# 1_Power.net
KiCad netlist of a schematic drawn in Altium Designer
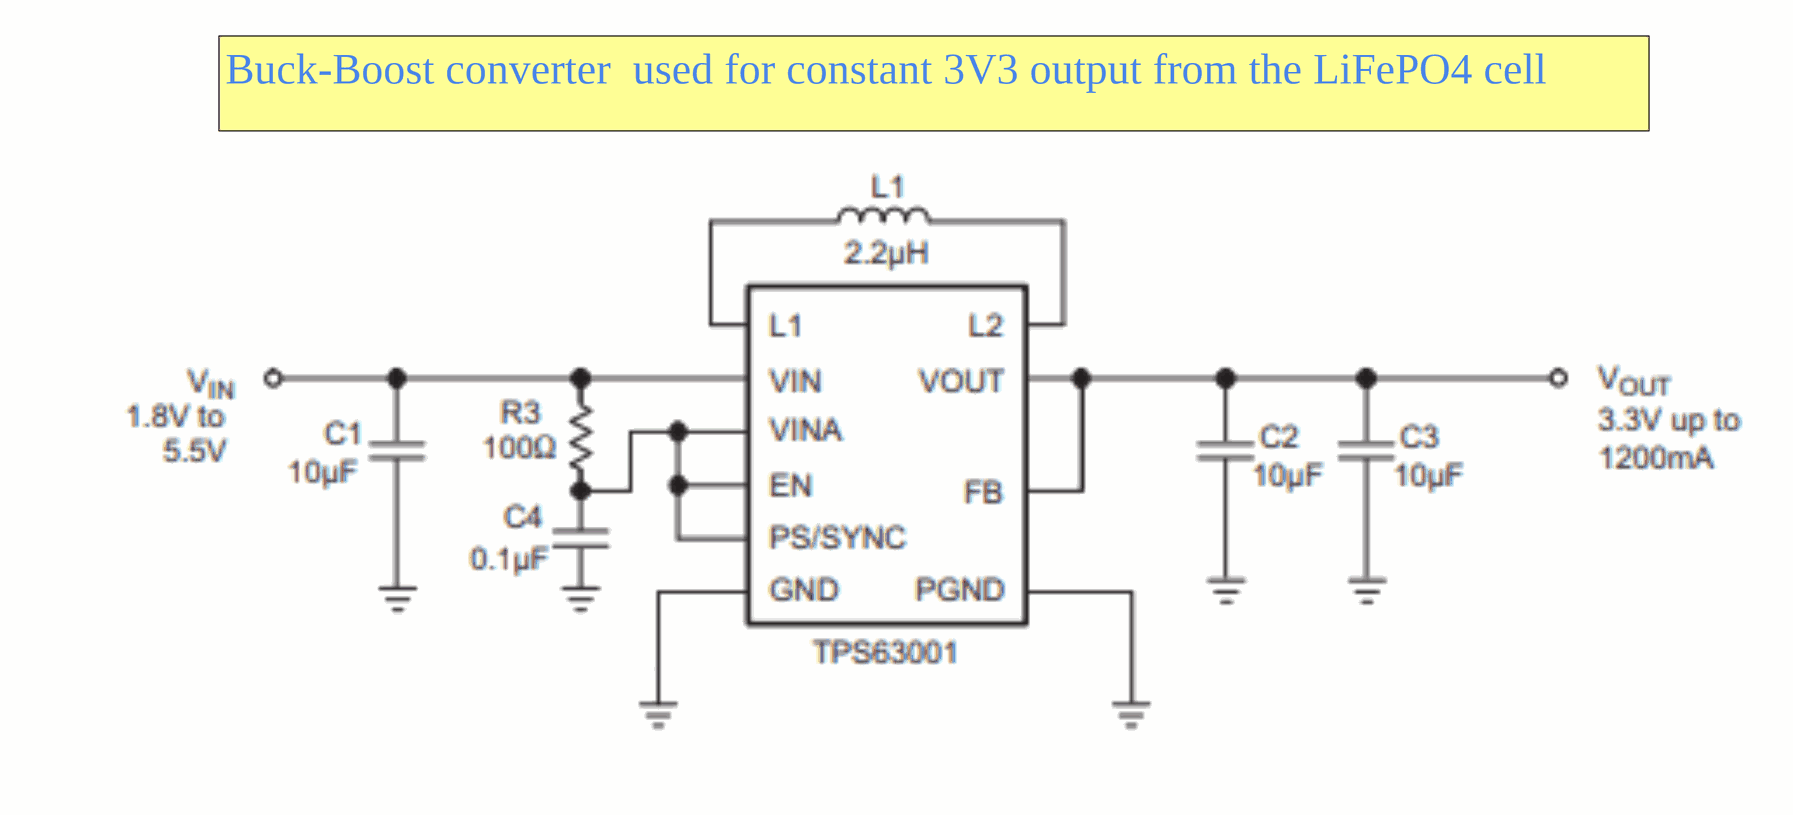
[diagram p0: 1_Power.SchDoc, top left]
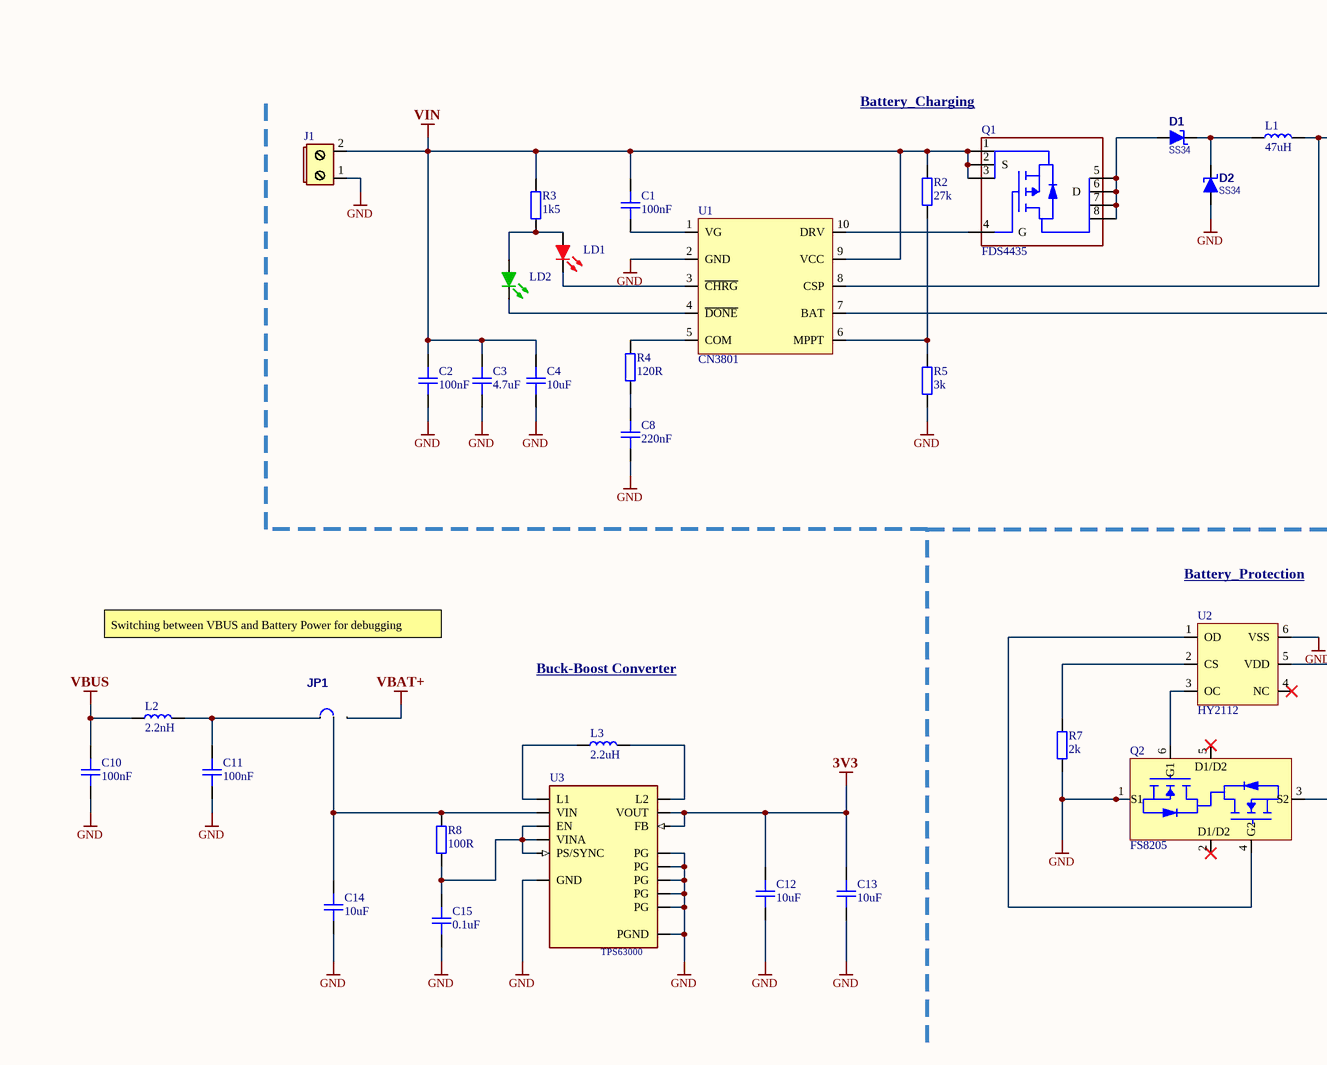
[diagram p1: 1_Power.SchDoc, top middle]
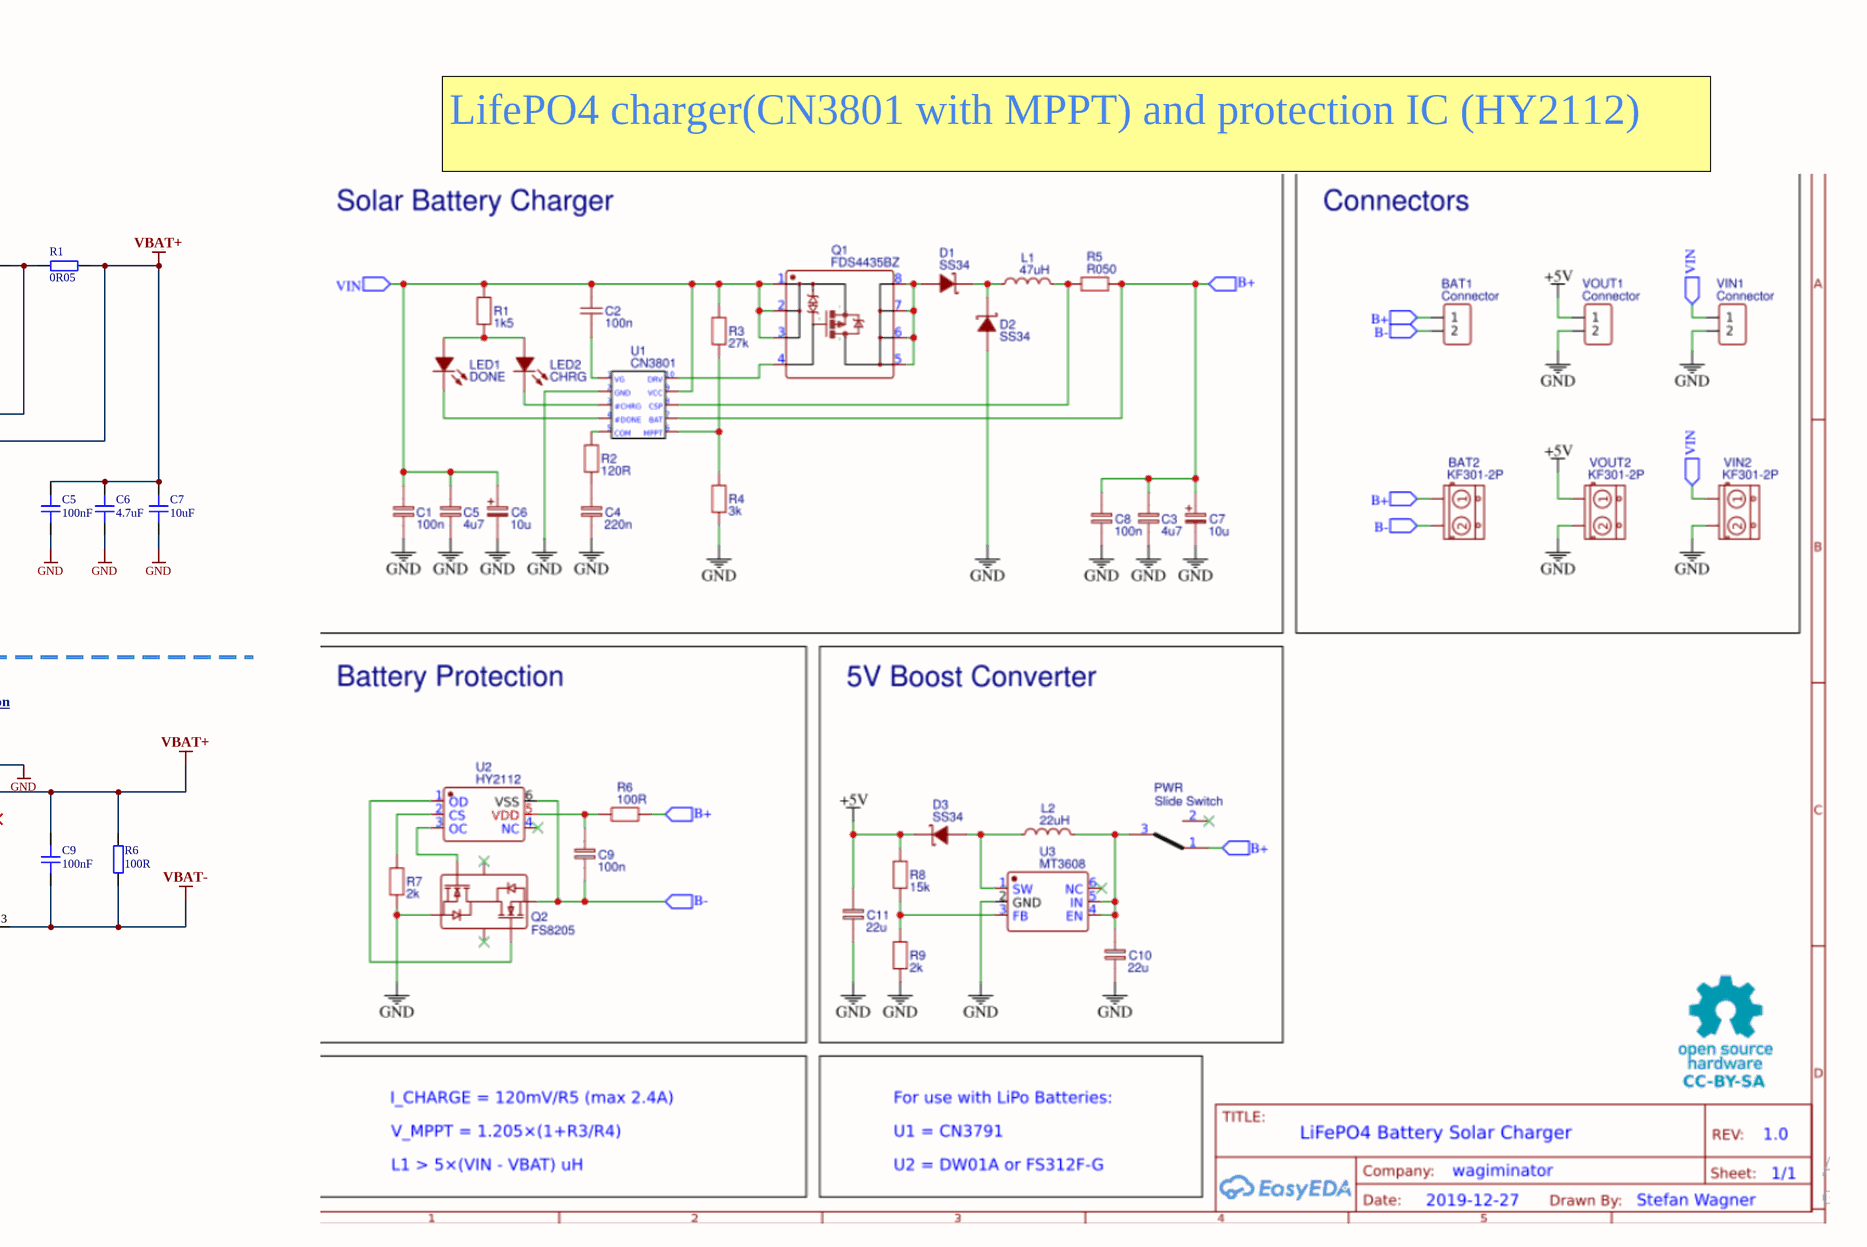
[diagram p2: 1_Power.SchDoc, top right]
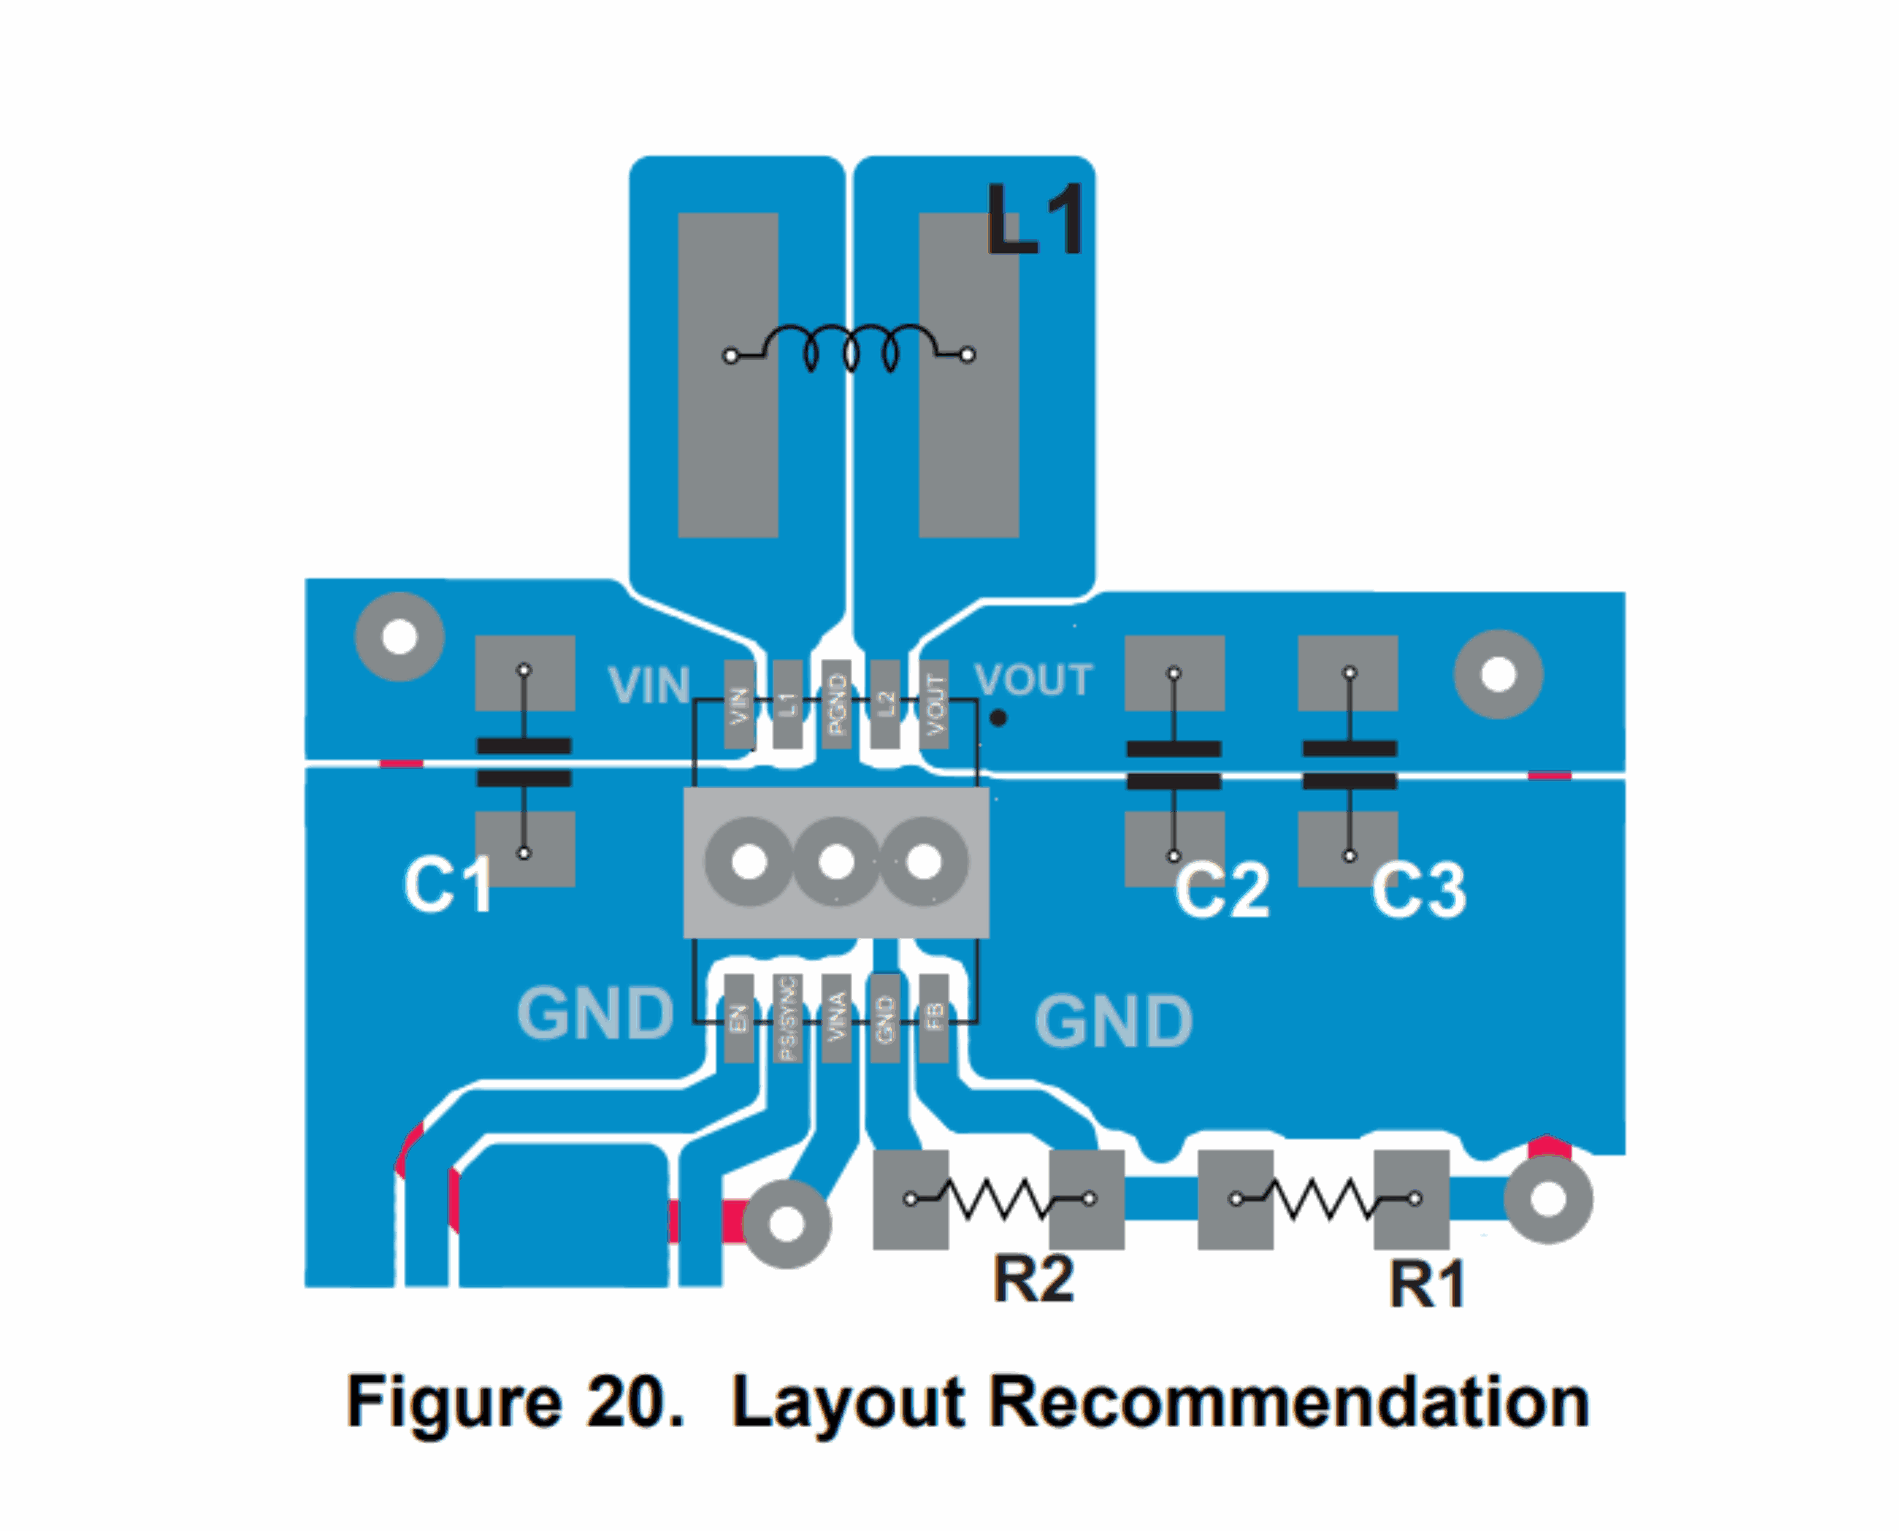
[diagram p3: 1_Power.SchDoc, bottom left]

(export (version "E")
  (design (tool "Eeschema 10.0.6"))
  (components
    (comp (ref "C1")
      (value "100nF")
      (footprint "CAP_0603")
      (description "Capacitor SMD 0603")
      (libsource (lib "Schlib1") (part "CAP_0603"))
    )
    (comp (ref "C2")
      (value "100nF")
      (footprint "CAP_0603")
      (description "Capacitor SMD 0603")
      (libsource (lib "Schlib1") (part "CAP_0603"))
    )
    (comp (ref "C3")
      (value "4.7uF")
      (footprint "CAP_0603")
      (description "Capacitor SMD 0603")
      (libsource (lib "Schlib1") (part "CAP_0603"))
    )
    (comp (ref "C4")
      (value "10uF")
      (footprint "CAP_0805")
      (description "Capacitor SMD 0805")
      (libsource (lib "Schlib1") (part "CAP_0805"))
    )
    (comp (ref "C5")
      (value "100nF")
      (footprint "CAP_0603")
      (description "Capacitor SMD 0603")
      (libsource (lib "Schlib1") (part "CAP_0603"))
    )
    (comp (ref "C6")
      (value "4.7uF")
      (footprint "CAP_0603")
      (description "Capacitor SMD 0603")
      (libsource (lib "Schlib1") (part "CAP_0603"))
    )
    (comp (ref "C7")
      (value "10uF")
      (footprint "CAP_0805")
      (description "Capacitor SMD 0805")
      (libsource (lib "Schlib1") (part "CAP_0805"))
    )
    (comp (ref "C8")
      (value "220nF")
      (footprint "CAP_0603")
      (description "Capacitor SMD 0603")
      (libsource (lib "Schlib1") (part "CAP_0603"))
    )
    (comp (ref "C9")
      (value "100nF")
      (footprint "CAP_0603")
      (description "Capacitor SMD 0603")
      (libsource (lib "Schlib1") (part "CAP_0603"))
    )
    (comp (ref "C10")
      (value "100nF")
      (footprint "CAP_0603")
      (description "Capacitor SMD 0603")
      (libsource (lib "Schlib1") (part "CAP_0603"))
    )
    (comp (ref "C11")
      (value "100nF")
      (footprint "CAP_0603")
      (description "Capacitor SMD 0603")
      (libsource (lib "Schlib1") (part "CAP_0603"))
    )
    (comp (ref "C12")
      (value "10uF")
      (footprint "CAP_0805")
      (description "Capacitor SMD 0805")
      (libsource (lib "Schlib1") (part "CAP_0805"))
    )
    (comp (ref "C13")
      (value "10uF")
      (footprint "CAP_0805")
      (description "Capacitor SMD 0805")
      (libsource (lib "Schlib1") (part "CAP_0805"))
    )
    (comp (ref "C14")
      (value "10uF")
      (footprint "CAP_0805")
      (description "Capacitor SMD 0805")
      (libsource (lib "Schlib1") (part "CAP_0805"))
    )
    (comp (ref "C15")
      (value "0.1uF")
      (footprint "CAP_0603")
      (description "Capacitor SMD 0603")
      (libsource (lib "Schlib1") (part "CAP_0603"))
    )
    (comp (ref "D1")
      (value "SS34")
      (footprint "DO-213AA")
      (description "Diode")
      (libsource (lib "Schlib1") (part "DIODE_SCHOTTKY"))
    )
    (comp (ref "D2")
      (value "SS34")
      (footprint "DO-213AA")
      (description "Diode")
      (libsource (lib "Schlib1") (part "DIODE_SCHOTTKY"))
    )
    (comp (ref "J1")
      (value "PLUGIN_TERMINAL")
      (description "Screw terminal or plug terminal for power")
      (libsource (lib "Schlib1") (part "Power_Connector"))
    )
    (comp (ref "JP1")
      (value "JUMPER_3PIN")
      (footprint "JUMPER_SMD_3")
      (libsource (lib "Schlib1") (part "JUMPER_3PIN"))
    )
    (comp (ref "L1")
      (value "47uH")
      (footprint "IND_0603")
      (description "Inductor SMD 0603")
      (libsource (lib "Schlib1") (part "IND_0603"))
    )
    (comp (ref "L2")
      (value "2.2nH")
      (footprint "IND_1008")
      (description "Inductor SMD 1008")
      (libsource (lib "Schlib1") (part "IND_1008"))
    )
    (comp (ref "L3")
      (value "2.2uH")
      (footprint "IND_1008")
      (description "Inductor SMD 1008")
      (libsource (lib "Schlib1") (part "IND_1008"))
    )
    (comp (ref "LD1")
      (value "LED_RED")
      (footprint "3.5X2.8X1.9")
      (description "Typical BLUE SiC LED")
      (fields (field (name "PUBLISHER") "Altium Limited"))
      (libsource (lib "Schlib1") (part "LED_RED"))
    )
    (comp (ref "LD2")
      (value "LED_GREEN")
      (footprint "3.5X2.8X1.9")
      (description "Typical BLUE SiC LED")
      (fields (field (name "PUBLISHER") "Altium Limited"))
      (libsource (lib "Schlib1") (part "LED_GREEN"))
    )
    (comp (ref "Q1") (value "FDS4435") (libsource (lib "Schlib1") (part "FDS4435")))
    (comp (ref "Q2") (value "FS8205") (libsource (lib "Schlib1") (part "FS8205")))
    (comp (ref "R1")
      (value "0R05")
      (footprint "RES_0805")
      (description "Resistor SMD 0805")
      (libsource (lib "Schlib1") (part "RES_0805"))
    )
    (comp (ref "R2")
      (value "27k")
      (footprint "RES_0603")
      (description "Resistor SMD 0603")
      (libsource (lib "Schlib1") (part "RES_0603"))
    )
    (comp (ref "R3")
      (value "1k5")
      (footprint "RES_0603")
      (description "Resistor SMD 0603")
      (libsource (lib "Schlib1") (part "RES_0603"))
    )
    (comp (ref "R4")
      (value "120R")
      (footprint "RES_0603")
      (description "Resistor SMD 0603")
      (libsource (lib "Schlib1") (part "RES_0603"))
    )
    (comp (ref "R5")
      (value "3k")
      (footprint "RES_0603")
      (description "Resistor SMD 0603")
      (libsource (lib "Schlib1") (part "RES_0603"))
    )
    (comp (ref "R6")
      (value "100R")
      (footprint "RES_0603")
      (description "Resistor SMD 0603")
      (libsource (lib "Schlib1") (part "RES_0603"))
    )
    (comp (ref "R7")
      (value "2k")
      (footprint "RES_0603")
      (description "Resistor SMD 0603")
      (libsource (lib "Schlib1") (part "RES_0603_1"))
    )
    (comp (ref "R8")
      (value "100R")
      (footprint "RES_0603")
      (description "Resistor SMD 0603")
      (libsource (lib "Schlib1") (part "RES_0603"))
    )
    (comp (ref "U1") (value "CN3801") (libsource (lib "Schlib1") (part "CN3801")))
    (comp (ref "U2")
      (value "HY2112")
      (description "LiFePO4 protection IC")
      (libsource (lib "Schlib1") (part "HY2112"))
    )
    (comp (ref "U3")
      (value "TPS63000_1")
      (footprint "SnapEDApcb:10-VFDFN")
      (fields (field (name "MP") "TPS63000") (field (name "MF") "Texas Instruments"))
      (libsource (lib "Schlib1") (part "TPS63000_1"))
    )
  )
  (nets
    (net (code "1") (name "3V3") (class "Default")
      (node (ref "C12") (pin "2") (pinfunction "2_2") (pintype "passive"))
      (node (ref "C13") (pin "2") (pinfunction "2_2") (pintype "passive"))
      (node (ref "U3") (pin "1") (pinfunction "VOUT_1") (pintype "power_in"))
      (node (ref "U3") (pin "10") (pinfunction "FB_10") (pintype "input"))
    )
    (net (code "2") (name "GND") (class "Default")
      (node (ref "C10") (pin "1") (pinfunction "1_1") (pintype "passive"))
      (node (ref "C11") (pin "1") (pinfunction "1_1") (pintype "passive"))
      (node (ref "C12") (pin "1") (pinfunction "1_1") (pintype "passive"))
      (node (ref "C13") (pin "1") (pinfunction "1_1") (pintype "passive"))
      (node (ref "C14") (pin "1") (pinfunction "1_1") (pintype "passive"))
      (node (ref "C15") (pin "1") (pinfunction "1_1") (pintype "passive"))
      (node (ref "C2") (pin "1") (pinfunction "1_1") (pintype "passive"))
      (node (ref "C3") (pin "1") (pinfunction "1_1") (pintype "passive"))
      (node (ref "C4") (pin "1") (pinfunction "1_1") (pintype "passive"))
      (node (ref "C5") (pin "1") (pinfunction "1_1") (pintype "passive"))
      (node (ref "C6") (pin "1") (pinfunction "1_1") (pintype "passive"))
      (node (ref "C7") (pin "1") (pinfunction "1_1") (pintype "passive"))
      (node (ref "C8") (pin "1") (pinfunction "1_1") (pintype "passive"))
      (node (ref "D2") (pin "1") (pinfunction "A_1") (pintype "passive"))
      (node (ref "J1") (pin "1") (pinfunction "1_1") (pintype "passive"))
      (node (ref "Q2") (pin "1") (pinfunction "S1_1") (pintype "passive"))
      (node (ref "R5") (pin "1") (pinfunction "1_1") (pintype "passive"))
      (node (ref "R7") (pin "1") (pinfunction "1_1") (pintype "passive"))
      (node (ref "U1") (pin "2") (pinfunction "GND_2") (pintype "passive"))
      (node (ref "U2") (pin "6") (pinfunction "VSS_6") (pintype "passive"))
      (node (ref "U3") (pin "3") (pinfunction "PGND_3") (pintype "power_in"))
      (node (ref "U3") (pin "9") (pinfunction "GND_9") (pintype "power_in"))
      (node (ref "U3") (pin "P$1") (pinfunction "PG_P$1") (pintype "power_in"))
      (node (ref "U3") (pin "P$2") (pinfunction "PG_P$2") (pintype "power_in"))
      (node (ref "U3") (pin "P$3") (pinfunction "PG_P$3") (pintype "power_in"))
      (node (ref "U3") (pin "P$4") (pinfunction "PG_P$4") (pintype "power_in"))
      (node (ref "U3") (pin "P$5") (pinfunction "PG_P$5") (pintype "power_in"))
    )
    (net (code "3") (name "Net-(C8-Pad2)") (class "Default")
      (node (ref "C8") (pin "2") (pinfunction "2_2") (pintype "passive"))
      (node (ref "R4") (pin "1") (pinfunction "1_1") (pintype "passive"))
    )
    (net (code "4") (name "Net-(C11-Pad2)") (class "Default")
      (node (ref "C11") (pin "2") (pinfunction "2_2") (pintype "passive"))
      (node (ref "JP1") (pin "1") (pinfunction "1_1") (pintype "passive"))
      (node (ref "L2") (pin "2") (pinfunction "2_2") (pintype "passive"))
    )
    (net (code "5") (name "Net-(D1-A)") (class "Default")
      (node (ref "D1") (pin "1") (pinfunction "A_1") (pintype "passive"))
      (node (ref "Q1") (pin "5") (pinfunction "D_5") (pintype "passive"))
      (node (ref "Q1") (pin "6") (pinfunction "D_6") (pintype "passive"))
      (node (ref "Q1") (pin "7") (pinfunction "D_7") (pintype "passive"))
      (node (ref "Q1") (pin "8") (pinfunction "D_8") (pintype "passive"))
    )
    (net (code "6") (name "Net-(D1-K)") (class "Default")
      (node (ref "D1") (pin "2") (pinfunction "K_2") (pintype "passive"))
      (node (ref "D2") (pin "2") (pinfunction "K_2") (pintype "passive"))
      (node (ref "L1") (pin "1") (pinfunction "1_1") (pintype "passive"))
    )
    (net (code "7") (name "Net-(LD1-A)") (class "Default")
      (node (ref "LD1") (pin "1") (pinfunction "A_1") (pintype "passive"))
      (node (ref "LD2") (pin "1") (pinfunction "A_1") (pintype "passive"))
      (node (ref "R3") (pin "1") (pinfunction "1_1") (pintype "passive"))
    )
    (net (code "8") (name "Net-(LD1-K)") (class "Default")
      (node (ref "LD1") (pin "2") (pinfunction "K_2") (pintype "passive"))
      (node (ref "U1") (pin "3") (pinfunction "CHRG_3") (pintype "passive"))
    )
    (net (code "9") (name "Net-(LD2-K)") (class "Default")
      (node (ref "LD2") (pin "2") (pinfunction "K_2") (pintype "passive"))
      (node (ref "U1") (pin "4") (pinfunction "DONE_4") (pintype "passive"))
    )
    (net (code "10") (name "Net-(Q1-G)") (class "Default")
      (node (ref "Q1") (pin "4") (pinfunction "G_4") (pintype "passive"))
      (node (ref "U1") (pin "10") (pinfunction "DRV_10") (pintype "passive"))
    )
    (net (code "11") (name "Net-(Q2-G1)") (class "Default")
      (node (ref "Q2") (pin "6") (pinfunction "G1_6") (pintype "passive"))
      (node (ref "U2") (pin "3") (pinfunction "OC_3") (pintype "passive"))
    )
    (net (code "12") (name "Net-(Q2-G2)") (class "Default")
      (node (ref "Q2") (pin "4") (pinfunction "G2_4") (pintype "passive"))
      (node (ref "U2") (pin "1") (pinfunction "OD_1") (pintype "passive"))
    )
    (net (code "13") (name "Net-(U1-COM)") (class "Default")
      (node (ref "R4") (pin "2") (pinfunction "2_2") (pintype "passive"))
      (node (ref "U1") (pin "5") (pinfunction "COM_5") (pintype "passive"))
    )
    (net (code "14") (name "Net-(U1-CSP)") (class "Default")
      (node (ref "L1") (pin "2") (pinfunction "2_2") (pintype "passive"))
      (node (ref "R1") (pin "1") (pinfunction "1_1") (pintype "passive"))
      (node (ref "U1") (pin "8") (pinfunction "CSP_8") (pintype "passive"))
    )
    (net (code "15") (name "Net-(U1-MPPT)") (class "Default")
      (node (ref "R2") (pin "1") (pinfunction "1_1") (pintype "passive"))
      (node (ref "R5") (pin "2") (pinfunction "2_2") (pintype "passive"))
      (node (ref "U1") (pin "6") (pinfunction "MPPT_6") (pintype "passive"))
    )
    (net (code "16") (name "Net-(U1-VG)") (class "Default")
      (node (ref "C1") (pin "1") (pinfunction "1_1") (pintype "passive"))
      (node (ref "U1") (pin "1") (pinfunction "VG_1") (pintype "passive"))
    )
    (net (code "17") (name "Net-(U2-CS)") (class "Default")
      (node (ref "R7") (pin "2") (pinfunction "2_2") (pintype "passive"))
      (node (ref "U2") (pin "2") (pinfunction "CS_2") (pintype "passive"))
    )
    (net (code "18") (name "Net-(U3-EN)") (class "Default")
      (node (ref "C15") (pin "2") (pinfunction "2_2") (pintype "passive"))
      (node (ref "R8") (pin "1") (pinfunction "1_1") (pintype "passive"))
      (node (ref "U3") (pin "6") (pinfunction "EN_6") (pintype "bidirectional"))
      (node (ref "U3") (pin "7") (pinfunction "PS/SYNC_7") (pintype "input"))
      (node (ref "U3") (pin "8") (pinfunction "VINA_8") (pintype "power_in"))
    )
    (net (code "19") (name "Net-(U3-L1)") (class "Default")
      (node (ref "L3") (pin "1") (pinfunction "1_1") (pintype "passive"))
      (node (ref "U3") (pin "4") (pinfunction "L1_4") (pintype "passive"))
    )
    (net (code "20") (name "Net-(U3-L2)") (class "Default")
      (node (ref "L3") (pin "2") (pinfunction "2_2") (pintype "passive"))
      (node (ref "U3") (pin "2") (pinfunction "L2_2") (pintype "passive"))
    )
    (net (code "21") (name "Net-(U3-VIN)") (class "Default")
      (node (ref "C14") (pin "2") (pinfunction "2_2") (pintype "passive"))
      (node (ref "JP1") (pin "2") (pinfunction "2_2") (pintype "passive"))
      (node (ref "R8") (pin "2") (pinfunction "2_2") (pintype "passive"))
      (node (ref "U3") (pin "5") (pinfunction "VIN_5") (pintype "power_in"))
    )
    (net (code "22") (name "VBAT+") (class "Default")
      (node (ref "C5") (pin "2") (pinfunction "2_2") (pintype "passive"))
      (node (ref "C6") (pin "2") (pinfunction "2_2") (pintype "passive"))
      (node (ref "C7") (pin "2") (pinfunction "2_2") (pintype "passive"))
      (node (ref "C9") (pin "2") (pinfunction "2_2") (pintype "passive"))
      (node (ref "JP1") (pin "3") (pinfunction "3_3") (pintype "passive"))
      (node (ref "R1") (pin "2") (pinfunction "2_2") (pintype "passive"))
      (node (ref "R6") (pin "2") (pinfunction "2_2") (pintype "passive"))
      (node (ref "U1") (pin "7") (pinfunction "BAT_7") (pintype "passive"))
      (node (ref "U2") (pin "5") (pinfunction "VDD_5") (pintype "passive"))
    )
    (net (code "23") (name "VBAT-") (class "Default")
      (node (ref "C9") (pin "1") (pinfunction "1_1") (pintype "passive"))
      (node (ref "Q2") (pin "3") (pinfunction "S2_3") (pintype "passive"))
      (node (ref "R6") (pin "1") (pinfunction "1_1") (pintype "passive"))
    )
    (net (code "24") (name "VBUS") (class "Default")
      (node (ref "C10") (pin "2") (pinfunction "2_2") (pintype "passive"))
      (node (ref "L2") (pin "1") (pinfunction "1_1") (pintype "passive"))
    )
    (net (code "25") (name "VIN") (class "Default")
      (node (ref "C1") (pin "2") (pinfunction "2_2") (pintype "passive"))
      (node (ref "C2") (pin "2") (pinfunction "2_2") (pintype "passive"))
      (node (ref "C3") (pin "2") (pinfunction "2_2") (pintype "passive"))
      (node (ref "C4") (pin "2") (pinfunction "2_2") (pintype "passive"))
      (node (ref "J1") (pin "2") (pinfunction "2_2") (pintype "passive"))
      (node (ref "Q1") (pin "1") (pinfunction "S_1") (pintype "passive"))
      (node (ref "Q1") (pin "2") (pinfunction "S_2") (pintype "passive"))
      (node (ref "Q1") (pin "3") (pinfunction "S_3") (pintype "passive"))
      (node (ref "R2") (pin "2") (pinfunction "2_2") (pintype "passive"))
      (node (ref "R3") (pin "2") (pinfunction "2_2") (pintype "passive"))
      (node (ref "U1") (pin "9") (pinfunction "VCC_9") (pintype "passive"))
    )
    (net (code "26") (name "unconnected-(Q2-D1{slash}D2-Pad2)") (class "Default")
      (node (ref "Q2") (pin "2") (pinfunction "D1/D2_2") (pintype "passive+no_connect"))
    )
    (net (code "27") (name "unconnected-(Q2-D1{slash}D2-Pad5)") (class "Default")
      (node (ref "Q2") (pin "5") (pinfunction "D1/D2_5") (pintype "passive+no_connect"))
    )
    (net (code "28") (name "unconnected-(U2-NC-Pad4)") (class "Default")
      (node (ref "U2") (pin "4") (pinfunction "NC_4") (pintype "passive+no_connect"))
    )
  )
)
